# microprocessor.net
KiCad netlist of a schematic drawn in Altium Designer
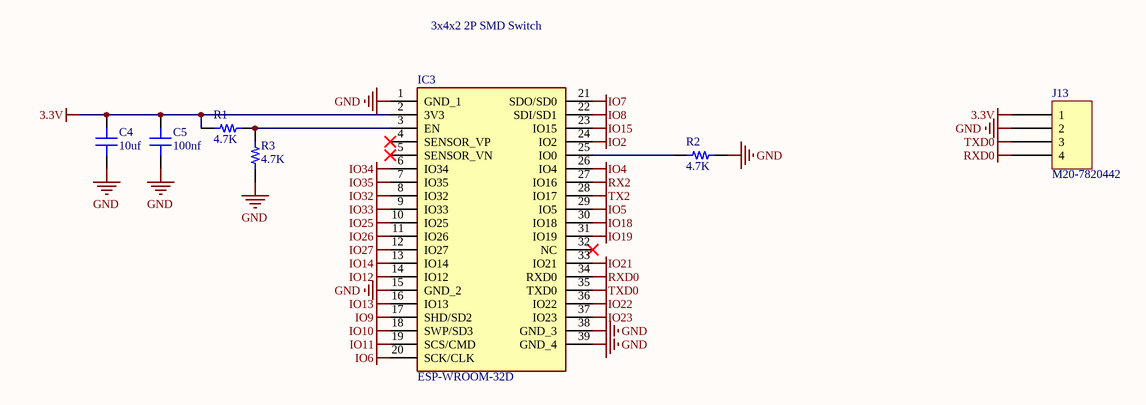
[diagram p0: microprocessor.SchDoc]

(export (version "E")
  (design (tool "Eeschema 10.0.6"))
  (components
    (comp (ref "C4")
      (value "10uf")
      (footprint "CAP 1206_3216 - 0.8MM")
      (description "CAP CER 1000PF 200V X7R 1206")
      (fields (field (name "PART NUMBER") "MM062C102KCZ2A") (field (name "MANUFACTURER") "AVX Corporation"))
      (libsource (lib "Celestial Altium Library - altium_library") (part "Capacitor"))
    )
    (comp (ref "C5")
      (value "100nf")
      (footprint "CAP 1206_3216 - 0.8MM")
      (description "CAP CER 1000PF 200V X7R 1206")
      (fields (field (name "PART NUMBER") "MM062C102KCZ2A") (field (name "MANUFACTURER") "AVX Corporation"))
      (libsource (lib "Celestial Altium Library - altium_library") (part "Capacitor"))
    )
    (comp (ref "IC3")
      (value "ESP-WROOM-32D")
      (footprint "SamacSys:ESPWROOM32D")
      (description "Integrated Circuit")
      (fields (field (name "MOUSER PART NUMBER") "356-ESP-WROOM-32D"))
      (libsource (lib "*") (part "ESP-WROOM-32D"))
    )
    (comp (ref "J13")
      (value "M20-7820442")
      (footprint "HARWIN M20-7820445")
      (description "CONN RCPT 4POS 0.1 GOLD PCB")
      (fields (field (name "MANUFACTURER") "Harwin Inc."))
      (libsource (lib "Celestial Altium Library - altium_library") (part "4 Pin"))
    )
    (comp (ref "R1")
      (value "4.7K")
      (footprint "RES 1206_3216")
      (description "RES SMD 61.9K OHM 1% 1/4W 1206")
      (fields (field (name "PART NUMBER") "CRCW120661K9FKEA") (field (name "MANUFACTURER") "Vishay Dale"))
      (libsource (lib "Celestial Altium Library - altium_library") (part "Resistor"))
    )
    (comp (ref "R2")
      (value "4.7K")
      (footprint "RES 1206_3216")
      (description "RES SMD 61.9K OHM 1% 1/4W 1206")
      (fields (field (name "PART NUMBER") "CRCW120661K9FKEA") (field (name "MANUFACTURER") "Vishay Dale"))
      (libsource (lib "Celestial Altium Library - altium_library") (part "Resistor"))
    )
    (comp (ref "R3")
      (value "4.7K")
      (footprint "RES 1206_3216")
      (description "RES SMD 61.9K OHM 1% 1/4W 1206")
      (fields (field (name "PART NUMBER") "CRCW120661K9FKEA") (field (name "MANUFACTURER") "Vishay Dale"))
      (libsource (lib "Celestial Altium Library - altium_library") (part "Resistor"))
    )
  )
  (nets
    (net (code "1") (name "3.3V") (class "Default")
      (node (ref "C4") (pin "2") (pinfunction "2_2") (pintype "passive"))
      (node (ref "C5") (pin "2") (pinfunction "2_2") (pintype "passive"))
      (node (ref "IC3") (pin "2") (pinfunction "3V3_2") (pintype "passive"))
      (node (ref "J13") (pin "1") (pinfunction "1_1") (pintype "passive"))
      (node (ref "R1") (pin "2") (pinfunction "2_2") (pintype "passive"))
    )
    (net (code "2") (name "GND") (class "Default")
      (node (ref "C4") (pin "1") (pinfunction "1_1") (pintype "passive"))
      (node (ref "C5") (pin "1") (pinfunction "1_1") (pintype "passive"))
      (node (ref "IC3") (pin "1") (pinfunction "GND_1_1") (pintype "passive"))
      (node (ref "IC3") (pin "15") (pinfunction "GND_2_15") (pintype "passive"))
      (node (ref "IC3") (pin "38") (pinfunction "GND_3_38") (pintype "passive"))
      (node (ref "IC3") (pin "39") (pinfunction "GND_4_39") (pintype "passive"))
      (node (ref "J13") (pin "2") (pinfunction "2_2") (pintype "passive"))
      (node (ref "R2") (pin "1") (pinfunction "1_1") (pintype "passive"))
      (node (ref "R3") (pin "2") (pinfunction "2_2") (pintype "passive"))
    )
    (net (code "3") (name "IO2") (class "Default")
      (node (ref "IC3") (pin "24") (pinfunction "IO2_24") (pintype "passive"))
    )
    (net (code "4") (name "IO4") (class "Default")
      (node (ref "IC3") (pin "26") (pinfunction "IO4_26") (pintype "passive"))
    )
    (net (code "5") (name "IO5") (class "Default")
      (node (ref "IC3") (pin "29") (pinfunction "IO5_29") (pintype "passive"))
    )
    (net (code "6") (name "IO6") (class "Default")
      (node (ref "IC3") (pin "20") (pinfunction "SCK/CLK_20") (pintype "passive"))
    )
    (net (code "7") (name "IO7") (class "Default")
      (node (ref "IC3") (pin "21") (pinfunction "SDO/SD0_21") (pintype "passive"))
    )
    (net (code "8") (name "IO8") (class "Default")
      (node (ref "IC3") (pin "22") (pinfunction "SDI/SD1_22") (pintype "passive"))
    )
    (net (code "9") (name "IO9") (class "Default")
      (node (ref "IC3") (pin "17") (pinfunction "SHD/SD2_17") (pintype "passive"))
    )
    (net (code "10") (name "IO10") (class "Default")
      (node (ref "IC3") (pin "18") (pinfunction "SWP/SD3_18") (pintype "passive"))
    )
    (net (code "11") (name "IO11") (class "Default")
      (node (ref "IC3") (pin "19") (pinfunction "SCS/CMD_19") (pintype "passive"))
    )
    (net (code "12") (name "IO12") (class "Default")
      (node (ref "IC3") (pin "14") (pinfunction "IO12_14") (pintype "passive"))
    )
    (net (code "13") (name "IO13") (class "Default")
      (node (ref "IC3") (pin "16") (pinfunction "IO13_16") (pintype "passive"))
    )
    (net (code "14") (name "IO14") (class "Default")
      (node (ref "IC3") (pin "13") (pinfunction "IO14_13") (pintype "passive"))
    )
    (net (code "15") (name "IO15") (class "Default")
      (node (ref "IC3") (pin "23") (pinfunction "IO15_23") (pintype "passive"))
    )
    (net (code "16") (name "IO18") (class "Default")
      (node (ref "IC3") (pin "30") (pinfunction "IO18_30") (pintype "passive"))
    )
    (net (code "17") (name "IO19") (class "Default")
      (node (ref "IC3") (pin "31") (pinfunction "IO19_31") (pintype "passive"))
    )
    (net (code "18") (name "IO21") (class "Default")
      (node (ref "IC3") (pin "33") (pinfunction "IO21_33") (pintype "passive"))
    )
    (net (code "19") (name "IO22") (class "Default")
      (node (ref "IC3") (pin "36") (pinfunction "IO22_36") (pintype "passive"))
    )
    (net (code "20") (name "IO23") (class "Default")
      (node (ref "IC3") (pin "37") (pinfunction "IO23_37") (pintype "passive"))
    )
    (net (code "21") (name "IO25") (class "Default")
      (node (ref "IC3") (pin "10") (pinfunction "IO25_10") (pintype "passive"))
    )
    (net (code "22") (name "IO26") (class "Default")
      (node (ref "IC3") (pin "11") (pinfunction "IO26_11") (pintype "passive"))
    )
    (net (code "23") (name "IO27") (class "Default")
      (node (ref "IC3") (pin "12") (pinfunction "IO27_12") (pintype "passive"))
    )
    (net (code "24") (name "IO32") (class "Default")
      (node (ref "IC3") (pin "8") (pinfunction "IO32_8") (pintype "passive"))
    )
    (net (code "25") (name "IO33") (class "Default")
      (node (ref "IC3") (pin "9") (pinfunction "IO33_9") (pintype "passive"))
    )
    (net (code "26") (name "IO34") (class "Default")
      (node (ref "IC3") (pin "6") (pinfunction "IO34_6") (pintype "passive"))
    )
    (net (code "27") (name "IO35") (class "Default")
      (node (ref "IC3") (pin "7") (pinfunction "IO35_7") (pintype "passive"))
    )
    (net (code "28") (name "Net-(IC3-EN)") (class "Default")
      (node (ref "IC3") (pin "3") (pinfunction "EN_3") (pintype "passive"))
      (node (ref "R1") (pin "1") (pinfunction "1_1") (pintype "passive"))
      (node (ref "R3") (pin "1") (pinfunction "1_1") (pintype "passive"))
    )
    (net (code "29") (name "Net-(IC3-IO0)") (class "Default")
      (node (ref "IC3") (pin "25") (pinfunction "IO0_25") (pintype "passive"))
      (node (ref "R2") (pin "2") (pinfunction "2_2") (pintype "passive"))
    )
    (net (code "30") (name "RX2") (class "Default")
      (node (ref "IC3") (pin "27") (pinfunction "IO16_27") (pintype "passive"))
    )
    (net (code "31") (name "RXD0") (class "Default")
      (node (ref "IC3") (pin "34") (pinfunction "RXD0_34") (pintype "passive"))
      (node (ref "J13") (pin "4") (pinfunction "4_4") (pintype "passive"))
    )
    (net (code "32") (name "TX2") (class "Default")
      (node (ref "IC3") (pin "28") (pinfunction "IO17_28") (pintype "passive"))
    )
    (net (code "33") (name "TXD0") (class "Default")
      (node (ref "IC3") (pin "35") (pinfunction "TXD0_35") (pintype "passive"))
      (node (ref "J13") (pin "3") (pinfunction "3_3") (pintype "passive"))
    )
    (net (code "34") (name "unconnected-(IC3-NC-Pad32)") (class "Default")
      (node (ref "IC3") (pin "32") (pinfunction "NC_32") (pintype "passive+no_connect"))
    )
    (net (code "35") (name "unconnected-(IC3-SENSOR_VN-Pad5)") (class "Default")
      (node (ref "IC3") (pin "5") (pinfunction "SENSOR_VN_5") (pintype "passive+no_connect"))
    )
    (net (code "36") (name "unconnected-(IC3-SENSOR_VP-Pad4)") (class "Default")
      (node (ref "IC3") (pin "4") (pinfunction "SENSOR_VP_4") (pintype "passive+no_connect"))
    )
  )
)
